# PCB-MicroVU.net
KiCad netlist of a schematic drawn in EAGLE
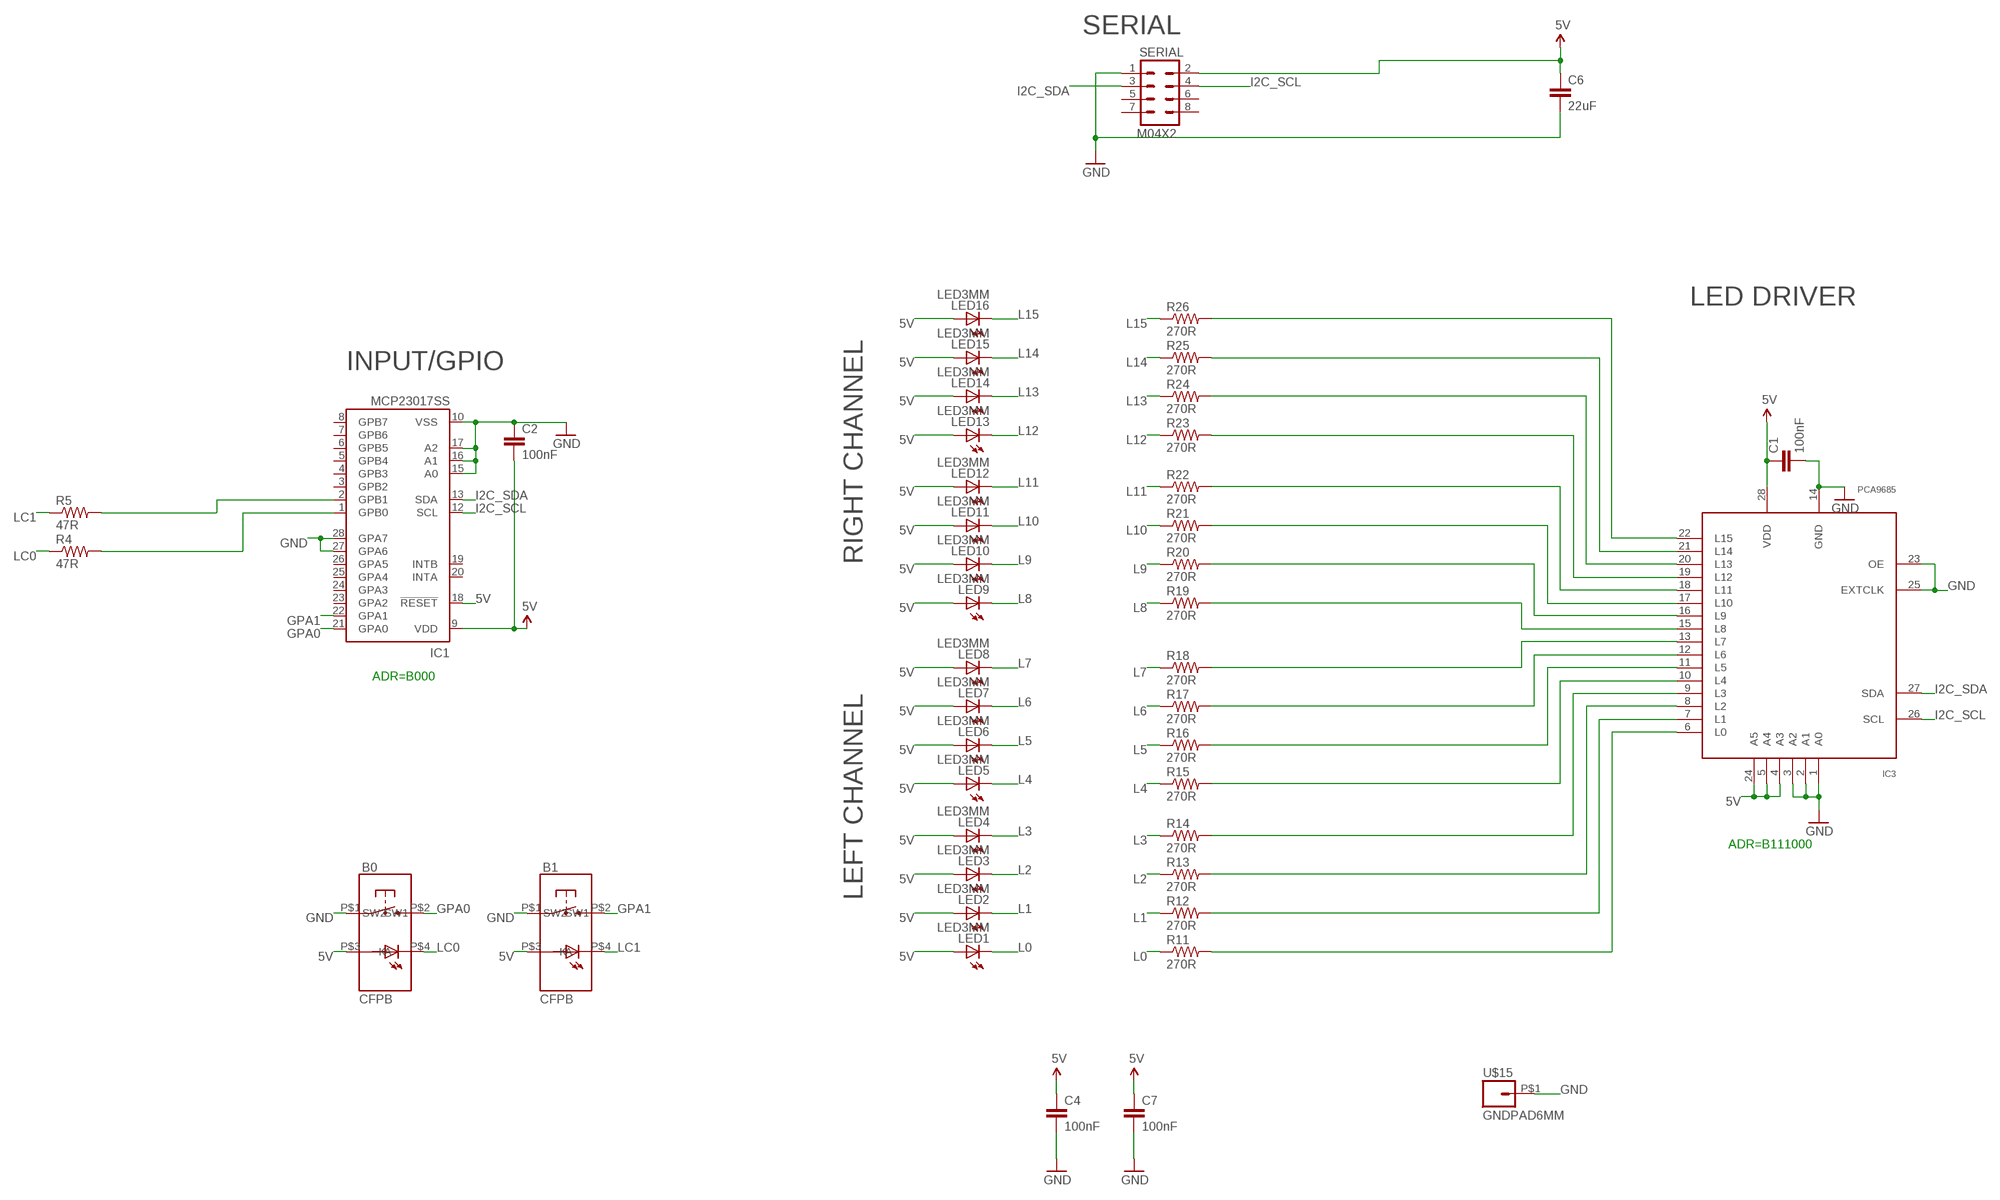
[diagram p0: schematic, sheet 1]

(export (version "E")
  (design (tool "Eeschema 10.0.6"))
  (components
    (comp (ref "B0")
      (value "CFPB")
      (footprint "eagle-import:CFPB-6_9MM")
      (libsource (lib "eagle-import") (part "CFPB"))
    )
    (comp (ref "B1")
      (value "CFPB")
      (footprint "eagle-import:CFPB-6_9MM")
      (libsource (lib "eagle-import") (part "CFPB"))
    )
    (comp (ref "C1")
      (value "100nF")
      (footprint "eagle-import:0603-CAP")
      (libsource (lib "eagle-import") (part "CAP0603-CAP"))
    )
    (comp (ref "C2")
      (value "100nF")
      (footprint "eagle-import:0603-CAP")
      (libsource (lib "eagle-import") (part "CAP0603-CAP"))
    )
    (comp (ref "C4")
      (value "100nF")
      (footprint "eagle-import:0603-CAP")
      (libsource (lib "eagle-import") (part "CAP0603-CAP"))
    )
    (comp (ref "C6")
      (value "22uF")
      (footprint "eagle-import:0805")
      (libsource (lib "eagle-import") (part "CAP0805"))
    )
    (comp (ref "C7")
      (value "100nF")
      (footprint "eagle-import:0603-CAP")
      (libsource (lib "eagle-import") (part "CAP0603-CAP"))
    )
    (comp (ref "IC1")
      (value "MCP23017SS")
      (footprint "eagle-import:SSOP28")
      (fields
        (field (name "MF") "MICROCHIP")
        (field (name "MPN") "MCP23017-E/SS")
        (field (name "MPN_1") "MCP23017-E/SS")
        (field (name "OC_FARNELL") "1467674")
        (field (name "OC_NEWARK") "31K2960")
      )
      (libsource (lib "eagle-import") (part "MCP23017SS"))
    )
    (comp (ref "IC3")
      (value "PCA9685")
      (footprint "eagle-import:TSSOP28")
      (libsource (lib "eagle-import") (part "PCA9685"))
    )
    (comp (ref "LED1")
      (value "LED3MM")
      (footprint "eagle-import:LED3MM")
      (libsource (lib "eagle-import") (part "LED3MM"))
    )
    (comp (ref "LED2")
      (value "LED3MM")
      (footprint "eagle-import:LED3MM")
      (libsource (lib "eagle-import") (part "LED3MM"))
    )
    (comp (ref "LED3")
      (value "LED3MM")
      (footprint "eagle-import:LED3MM")
      (libsource (lib "eagle-import") (part "LED3MM"))
    )
    (comp (ref "LED4")
      (value "LED3MM")
      (footprint "eagle-import:LED3MM")
      (libsource (lib "eagle-import") (part "LED3MM"))
    )
    (comp (ref "LED5")
      (value "LED3MM")
      (footprint "eagle-import:LED3MM")
      (libsource (lib "eagle-import") (part "LED3MM"))
    )
    (comp (ref "LED6")
      (value "LED3MM")
      (footprint "eagle-import:LED3MM")
      (libsource (lib "eagle-import") (part "LED3MM"))
    )
    (comp (ref "LED7")
      (value "LED3MM")
      (footprint "eagle-import:LED3MM")
      (libsource (lib "eagle-import") (part "LED3MM"))
    )
    (comp (ref "LED8")
      (value "LED3MM")
      (footprint "eagle-import:LED3MM")
      (libsource (lib "eagle-import") (part "LED3MM"))
    )
    (comp (ref "LED9")
      (value "LED3MM")
      (footprint "eagle-import:LED3MM")
      (libsource (lib "eagle-import") (part "LED3MM"))
    )
    (comp (ref "LED10")
      (value "LED3MM")
      (footprint "eagle-import:LED3MM")
      (libsource (lib "eagle-import") (part "LED3MM"))
    )
    (comp (ref "LED11")
      (value "LED3MM")
      (footprint "eagle-import:LED3MM")
      (libsource (lib "eagle-import") (part "LED3MM"))
    )
    (comp (ref "LED12")
      (value "LED3MM")
      (footprint "eagle-import:LED3MM")
      (libsource (lib "eagle-import") (part "LED3MM"))
    )
    (comp (ref "LED13")
      (value "LED3MM")
      (footprint "eagle-import:LED3MM")
      (libsource (lib "eagle-import") (part "LED3MM"))
    )
    (comp (ref "LED14")
      (value "LED3MM")
      (footprint "eagle-import:LED3MM")
      (libsource (lib "eagle-import") (part "LED3MM"))
    )
    (comp (ref "LED15")
      (value "LED3MM")
      (footprint "eagle-import:LED3MM")
      (libsource (lib "eagle-import") (part "LED3MM"))
    )
    (comp (ref "LED16")
      (value "LED3MM")
      (footprint "eagle-import:LED3MM")
      (libsource (lib "eagle-import") (part "LED3MM"))
    )
    (comp (ref "R4")
      (value "47R")
      (footprint "eagle-import:0603-RES")
      (libsource (lib "eagle-import") (part "RESISTOR0603-RES"))
    )
    (comp (ref "R5")
      (value "47R")
      (footprint "eagle-import:0603-RES")
      (libsource (lib "eagle-import") (part "RESISTOR0603-RES"))
    )
    (comp (ref "R11")
      (value "270R")
      (footprint "eagle-import:0603-RES")
      (libsource (lib "eagle-import") (part "RESISTOR0603-RES"))
    )
    (comp (ref "R12")
      (value "270R")
      (footprint "eagle-import:0603-RES")
      (libsource (lib "eagle-import") (part "RESISTOR0603-RES"))
    )
    (comp (ref "R13")
      (value "270R")
      (footprint "eagle-import:0603-RES")
      (libsource (lib "eagle-import") (part "RESISTOR0603-RES"))
    )
    (comp (ref "R14")
      (value "270R")
      (footprint "eagle-import:0603-RES")
      (libsource (lib "eagle-import") (part "RESISTOR0603-RES"))
    )
    (comp (ref "R15")
      (value "270R")
      (footprint "eagle-import:0603-RES")
      (libsource (lib "eagle-import") (part "RESISTOR0603-RES"))
    )
    (comp (ref "R16")
      (value "270R")
      (footprint "eagle-import:0603-RES")
      (libsource (lib "eagle-import") (part "RESISTOR0603-RES"))
    )
    (comp (ref "R17")
      (value "270R")
      (footprint "eagle-import:0603-RES")
      (libsource (lib "eagle-import") (part "RESISTOR0603-RES"))
    )
    (comp (ref "R18")
      (value "270R")
      (footprint "eagle-import:0603-RES")
      (libsource (lib "eagle-import") (part "RESISTOR0603-RES"))
    )
    (comp (ref "R19")
      (value "270R")
      (footprint "eagle-import:0603-RES")
      (libsource (lib "eagle-import") (part "RESISTOR0603-RES"))
    )
    (comp (ref "R20")
      (value "270R")
      (footprint "eagle-import:0603-RES")
      (libsource (lib "eagle-import") (part "RESISTOR0603-RES"))
    )
    (comp (ref "R21")
      (value "270R")
      (footprint "eagle-import:0603-RES")
      (libsource (lib "eagle-import") (part "RESISTOR0603-RES"))
    )
    (comp (ref "R22")
      (value "270R")
      (footprint "eagle-import:0603-RES")
      (libsource (lib "eagle-import") (part "RESISTOR0603-RES"))
    )
    (comp (ref "R23")
      (value "270R")
      (footprint "eagle-import:0603-RES")
      (libsource (lib "eagle-import") (part "RESISTOR0603-RES"))
    )
    (comp (ref "R24")
      (value "270R")
      (footprint "eagle-import:0603-RES")
      (libsource (lib "eagle-import") (part "RESISTOR0603-RES"))
    )
    (comp (ref "R25")
      (value "270R")
      (footprint "eagle-import:0603-RES")
      (libsource (lib "eagle-import") (part "RESISTOR0603-RES"))
    )
    (comp (ref "R26")
      (value "270R")
      (footprint "eagle-import:0603-RES")
      (libsource (lib "eagle-import") (part "RESISTOR0603-RES"))
    )
    (comp (ref "SERIAL")
      (value "M04X2")
      (footprint "eagle-import:2X4")
      (libsource (lib "eagle-import") (part "M04X2"))
    )
    (comp (ref "U$15")
      (value "GNDPAD6MM")
      (footprint "eagle-import:3.2MMPAD6MM")
      (libsource (lib "eagle-import") (part "GNDPAD6MM"))
    )
  )
  (nets
    (net (code "1") (name "/GPA0") (class "Default")
      (node (ref "B0") (pin "P$2") (pinfunction "SW2_P$2") (pintype "bidirectional"))
      (node (ref "IC1") (pin "21") (pinfunction "GPA0_21") (pintype "bidirectional"))
    )
    (net (code "2") (name "/GPA1") (class "Default")
      (node (ref "B1") (pin "P$2") (pinfunction "SW2_P$2") (pintype "bidirectional"))
      (node (ref "IC1") (pin "22") (pinfunction "GPA1_22") (pintype "bidirectional"))
    )
    (net (code "3") (name "/I2C_SCL") (class "Default")
      (node (ref "IC1") (pin "12") (pinfunction "SCL_12") (pintype "input"))
      (node (ref "IC3") (pin "26") (pinfunction "SCL_26") (pintype "input"))
      (node (ref "SERIAL") (pin "4") (pinfunction "4_4") (pintype "passive"))
    )
    (net (code "4") (name "/I2C_SDA") (class "Default")
      (node (ref "IC1") (pin "13") (pinfunction "SDA_13") (pintype "bidirectional"))
      (node (ref "IC3") (pin "27") (pinfunction "SDA_27") (pintype "input"))
      (node (ref "SERIAL") (pin "3") (pinfunction "3_3") (pintype "passive"))
    )
    (net (code "5") (name "/L0") (class "Default")
      (node (ref "LED1") (pin "K") (pinfunction "C_K") (pintype "passive"))
      (node (ref "R11") (pin "1") (pinfunction "1_1") (pintype "passive"))
    )
    (net (code "6") (name "/L1") (class "Default")
      (node (ref "LED2") (pin "K") (pinfunction "C_K") (pintype "passive"))
      (node (ref "R12") (pin "1") (pinfunction "1_1") (pintype "passive"))
    )
    (net (code "7") (name "/L2") (class "Default")
      (node (ref "LED3") (pin "K") (pinfunction "C_K") (pintype "passive"))
      (node (ref "R13") (pin "1") (pinfunction "1_1") (pintype "passive"))
    )
    (net (code "8") (name "/L3") (class "Default")
      (node (ref "LED4") (pin "K") (pinfunction "C_K") (pintype "passive"))
      (node (ref "R14") (pin "1") (pinfunction "1_1") (pintype "passive"))
    )
    (net (code "9") (name "/L4") (class "Default")
      (node (ref "LED5") (pin "K") (pinfunction "C_K") (pintype "passive"))
      (node (ref "R15") (pin "1") (pinfunction "1_1") (pintype "passive"))
    )
    (net (code "10") (name "/L5") (class "Default")
      (node (ref "LED6") (pin "K") (pinfunction "C_K") (pintype "passive"))
      (node (ref "R16") (pin "1") (pinfunction "1_1") (pintype "passive"))
    )
    (net (code "11") (name "/L6") (class "Default")
      (node (ref "LED7") (pin "K") (pinfunction "C_K") (pintype "passive"))
      (node (ref "R17") (pin "1") (pinfunction "1_1") (pintype "passive"))
    )
    (net (code "12") (name "/L7") (class "Default")
      (node (ref "LED8") (pin "K") (pinfunction "C_K") (pintype "passive"))
      (node (ref "R18") (pin "1") (pinfunction "1_1") (pintype "passive"))
    )
    (net (code "13") (name "/L8") (class "Default")
      (node (ref "LED9") (pin "K") (pinfunction "C_K") (pintype "passive"))
      (node (ref "R19") (pin "1") (pinfunction "1_1") (pintype "passive"))
    )
    (net (code "14") (name "/L9") (class "Default")
      (node (ref "LED10") (pin "K") (pinfunction "C_K") (pintype "passive"))
      (node (ref "R20") (pin "1") (pinfunction "1_1") (pintype "passive"))
    )
    (net (code "15") (name "/L10") (class "Default")
      (node (ref "LED11") (pin "K") (pinfunction "C_K") (pintype "passive"))
      (node (ref "R21") (pin "1") (pinfunction "1_1") (pintype "passive"))
    )
    (net (code "16") (name "/L11") (class "Default")
      (node (ref "LED12") (pin "K") (pinfunction "C_K") (pintype "passive"))
      (node (ref "R22") (pin "1") (pinfunction "1_1") (pintype "passive"))
    )
    (net (code "17") (name "/L12") (class "Default")
      (node (ref "LED13") (pin "K") (pinfunction "C_K") (pintype "passive"))
      (node (ref "R23") (pin "1") (pinfunction "1_1") (pintype "passive"))
    )
    (net (code "18") (name "/L13") (class "Default")
      (node (ref "LED14") (pin "K") (pinfunction "C_K") (pintype "passive"))
      (node (ref "R24") (pin "1") (pinfunction "1_1") (pintype "passive"))
    )
    (net (code "19") (name "/L14") (class "Default")
      (node (ref "LED15") (pin "K") (pinfunction "C_K") (pintype "passive"))
      (node (ref "R25") (pin "1") (pinfunction "1_1") (pintype "passive"))
    )
    (net (code "20") (name "/L15") (class "Default")
      (node (ref "LED16") (pin "K") (pinfunction "C_K") (pintype "passive"))
      (node (ref "R26") (pin "1") (pinfunction "1_1") (pintype "passive"))
    )
    (net (code "21") (name "/LC0") (class "Default")
      (node (ref "B0") (pin "P$4") (pinfunction "K_P$4") (pintype "bidirectional"))
      (node (ref "R4") (pin "1") (pinfunction "1_1") (pintype "passive"))
    )
    (net (code "22") (name "/LC1") (class "Default")
      (node (ref "B1") (pin "P$4") (pinfunction "K_P$4") (pintype "bidirectional"))
      (node (ref "R5") (pin "1") (pinfunction "1_1") (pintype "passive"))
    )
    (net (code "23") (name "5V") (class "Default")
      (node (ref "B0") (pin "P$3") (pinfunction "A_P$3") (pintype "bidirectional"))
      (node (ref "B1") (pin "P$3") (pinfunction "A_P$3") (pintype "bidirectional"))
      (node (ref "C1") (pin "1") (pinfunction "1_1") (pintype "passive"))
      (node (ref "C2") (pin "2") (pinfunction "2_2") (pintype "passive"))
      (node (ref "C4") (pin "1") (pinfunction "1_1") (pintype "passive"))
      (node (ref "C6") (pin "1") (pinfunction "1_1") (pintype "passive"))
      (node (ref "C7") (pin "1") (pinfunction "1_1") (pintype "passive"))
      (node (ref "IC1") (pin "18") (pinfunction "~{RESET}_18") (pintype "input"))
      (node (ref "IC1") (pin "9") (pinfunction "VDD_9") (pintype "power_in"))
      (node (ref "IC3") (pin "24") (pinfunction "A5_24") (pintype "input"))
      (node (ref "IC3") (pin "28") (pinfunction "VDD_28") (pintype "power_in"))
      (node (ref "IC3") (pin "4") (pinfunction "A3_4") (pintype "input"))
      (node (ref "IC3") (pin "5") (pinfunction "A4_5") (pintype "input"))
      (node (ref "LED1") (pin "A") (pinfunction "A_A") (pintype "passive"))
      (node (ref "LED10") (pin "A") (pinfunction "A_A") (pintype "passive"))
      (node (ref "LED11") (pin "A") (pinfunction "A_A") (pintype "passive"))
      (node (ref "LED12") (pin "A") (pinfunction "A_A") (pintype "passive"))
      (node (ref "LED13") (pin "A") (pinfunction "A_A") (pintype "passive"))
      (node (ref "LED14") (pin "A") (pinfunction "A_A") (pintype "passive"))
      (node (ref "LED15") (pin "A") (pinfunction "A_A") (pintype "passive"))
      (node (ref "LED16") (pin "A") (pinfunction "A_A") (pintype "passive"))
      (node (ref "LED2") (pin "A") (pinfunction "A_A") (pintype "passive"))
      (node (ref "LED3") (pin "A") (pinfunction "A_A") (pintype "passive"))
      (node (ref "LED4") (pin "A") (pinfunction "A_A") (pintype "passive"))
      (node (ref "LED5") (pin "A") (pinfunction "A_A") (pintype "passive"))
      (node (ref "LED6") (pin "A") (pinfunction "A_A") (pintype "passive"))
      (node (ref "LED7") (pin "A") (pinfunction "A_A") (pintype "passive"))
      (node (ref "LED8") (pin "A") (pinfunction "A_A") (pintype "passive"))
      (node (ref "LED9") (pin "A") (pinfunction "A_A") (pintype "passive"))
      (node (ref "SERIAL") (pin "2") (pinfunction "2_2") (pintype "passive"))
    )
    (net (code "24") (name "GND") (class "Default")
      (node (ref "B0") (pin "P$1") (pinfunction "SW1_P$1") (pintype "bidirectional"))
      (node (ref "B1") (pin "P$1") (pinfunction "SW1_P$1") (pintype "bidirectional"))
      (node (ref "C1") (pin "2") (pinfunction "2_2") (pintype "passive"))
      (node (ref "C2") (pin "1") (pinfunction "1_1") (pintype "passive"))
      (node (ref "C4") (pin "2") (pinfunction "2_2") (pintype "passive"))
      (node (ref "C6") (pin "2") (pinfunction "2_2") (pintype "passive"))
      (node (ref "C7") (pin "2") (pinfunction "2_2") (pintype "passive"))
      (node (ref "IC1") (pin "10") (pinfunction "VSS_10") (pintype "power_in"))
      (node (ref "IC1") (pin "15") (pinfunction "A0_15") (pintype "input"))
      (node (ref "IC1") (pin "16") (pinfunction "A1_16") (pintype "input"))
      (node (ref "IC1") (pin "17") (pinfunction "A2_17") (pintype "input"))
      (node (ref "IC1") (pin "27") (pinfunction "GPA6_27") (pintype "bidirectional"))
      (node (ref "IC1") (pin "28") (pinfunction "GPA7_28") (pintype "bidirectional"))
      (node (ref "IC3") (pin "1") (pinfunction "A0_1") (pintype "input"))
      (node (ref "IC3") (pin "14") (pinfunction "GND_14") (pintype "power_in"))
      (node (ref "IC3") (pin "2") (pinfunction "A1_2") (pintype "input"))
      (node (ref "IC3") (pin "23") (pinfunction "OE_23") (pintype "input"))
      (node (ref "IC3") (pin "25") (pinfunction "EXTCLK_25") (pintype "input"))
      (node (ref "IC3") (pin "3") (pinfunction "A2_3") (pintype "input"))
      (node (ref "SERIAL") (pin "1") (pinfunction "1_1") (pintype "passive"))
      (node (ref "U$15") (pin "P$1") (pinfunction "1_P$1") (pintype "passive"))
    )
    (net (code "25") (name "Net-(IC1-GPB0)") (class "Default")
      (node (ref "IC1") (pin "1") (pinfunction "GPB0_1") (pintype "bidirectional"))
      (node (ref "R4") (pin "2") (pinfunction "2_2") (pintype "passive"))
    )
    (net (code "26") (name "Net-(IC1-GPB1)") (class "Default")
      (node (ref "IC1") (pin "2") (pinfunction "GPB1_2") (pintype "bidirectional"))
      (node (ref "R5") (pin "2") (pinfunction "2_2") (pintype "passive"))
    )
    (net (code "27") (name "Net-(IC3-L0)") (class "Default")
      (node (ref "IC3") (pin "6") (pinfunction "L0_6") (pintype "output"))
      (node (ref "R11") (pin "2") (pinfunction "2_2") (pintype "passive"))
    )
    (net (code "28") (name "Net-(IC3-L1)") (class "Default")
      (node (ref "IC3") (pin "7") (pinfunction "L1_7") (pintype "output"))
      (node (ref "R12") (pin "2") (pinfunction "2_2") (pintype "passive"))
    )
    (net (code "29") (name "Net-(IC3-L2)") (class "Default")
      (node (ref "IC3") (pin "8") (pinfunction "L2_8") (pintype "output"))
      (node (ref "R13") (pin "2") (pinfunction "2_2") (pintype "passive"))
    )
    (net (code "30") (name "Net-(IC3-L3)") (class "Default")
      (node (ref "IC3") (pin "9") (pinfunction "L3_9") (pintype "output"))
      (node (ref "R14") (pin "2") (pinfunction "2_2") (pintype "passive"))
    )
    (net (code "31") (name "Net-(IC3-L4)") (class "Default")
      (node (ref "IC3") (pin "10") (pinfunction "L4_10") (pintype "output"))
      (node (ref "R15") (pin "2") (pinfunction "2_2") (pintype "passive"))
    )
    (net (code "32") (name "Net-(IC3-L5)") (class "Default")
      (node (ref "IC3") (pin "11") (pinfunction "L5_11") (pintype "output"))
      (node (ref "R16") (pin "2") (pinfunction "2_2") (pintype "passive"))
    )
    (net (code "33") (name "Net-(IC3-L6)") (class "Default")
      (node (ref "IC3") (pin "12") (pinfunction "L6_12") (pintype "output"))
      (node (ref "R17") (pin "2") (pinfunction "2_2") (pintype "passive"))
    )
    (net (code "34") (name "Net-(IC3-L7)") (class "Default")
      (node (ref "IC3") (pin "13") (pinfunction "L7_13") (pintype "output"))
      (node (ref "R18") (pin "2") (pinfunction "2_2") (pintype "passive"))
    )
    (net (code "35") (name "Net-(IC3-L8)") (class "Default")
      (node (ref "IC3") (pin "15") (pinfunction "L8_15") (pintype "output"))
      (node (ref "R19") (pin "2") (pinfunction "2_2") (pintype "passive"))
    )
    (net (code "36") (name "Net-(IC3-L9)") (class "Default")
      (node (ref "IC3") (pin "16") (pinfunction "L9_16") (pintype "output"))
      (node (ref "R20") (pin "2") (pinfunction "2_2") (pintype "passive"))
    )
    (net (code "37") (name "Net-(IC3-L10)") (class "Default")
      (node (ref "IC3") (pin "17") (pinfunction "L10_17") (pintype "output"))
      (node (ref "R21") (pin "2") (pinfunction "2_2") (pintype "passive"))
    )
    (net (code "38") (name "Net-(IC3-L11)") (class "Default")
      (node (ref "IC3") (pin "18") (pinfunction "L11_18") (pintype "output"))
      (node (ref "R22") (pin "2") (pinfunction "2_2") (pintype "passive"))
    )
    (net (code "39") (name "Net-(IC3-L12)") (class "Default")
      (node (ref "IC3") (pin "19") (pinfunction "L12_19") (pintype "output"))
      (node (ref "R23") (pin "2") (pinfunction "2_2") (pintype "passive"))
    )
    (net (code "40") (name "Net-(IC3-L13)") (class "Default")
      (node (ref "IC3") (pin "20") (pinfunction "L13_20") (pintype "output"))
      (node (ref "R24") (pin "2") (pinfunction "2_2") (pintype "passive"))
    )
    (net (code "41") (name "Net-(IC3-L14)") (class "Default")
      (node (ref "IC3") (pin "21") (pinfunction "L14_21") (pintype "output"))
      (node (ref "R25") (pin "2") (pinfunction "2_2") (pintype "passive"))
    )
    (net (code "42") (name "Net-(IC3-L15)") (class "Default")
      (node (ref "IC3") (pin "22") (pinfunction "L15_22") (pintype "output"))
      (node (ref "R26") (pin "2") (pinfunction "2_2") (pintype "passive"))
    )
    (net (code "43") (name "unconnected-(IC1-GPA2-Pad23)") (class "Default")
      (node (ref "IC1") (pin "23") (pinfunction "GPA2_23") (pintype "bidirectional"))
    )
    (net (code "44") (name "unconnected-(IC1-GPA3-Pad24)") (class "Default")
      (node (ref "IC1") (pin "24") (pinfunction "GPA3_24") (pintype "bidirectional"))
    )
    (net (code "45") (name "unconnected-(IC1-GPA4-Pad25)") (class "Default")
      (node (ref "IC1") (pin "25") (pinfunction "GPA4_25") (pintype "bidirectional"))
    )
    (net (code "46") (name "unconnected-(IC1-GPA5-Pad26)") (class "Default")
      (node (ref "IC1") (pin "26") (pinfunction "GPA5_26") (pintype "bidirectional"))
    )
    (net (code "47") (name "unconnected-(IC1-GPB2-Pad3)") (class "Default")
      (node (ref "IC1") (pin "3") (pinfunction "GPB2_3") (pintype "bidirectional"))
    )
    (net (code "48") (name "unconnected-(IC1-GPB3-Pad4)") (class "Default")
      (node (ref "IC1") (pin "4") (pinfunction "GPB3_4") (pintype "bidirectional"))
    )
    (net (code "49") (name "unconnected-(IC1-GPB4-Pad5)") (class "Default")
      (node (ref "IC1") (pin "5") (pinfunction "GPB4_5") (pintype "bidirectional"))
    )
    (net (code "50") (name "unconnected-(IC1-GPB5-Pad6)") (class "Default")
      (node (ref "IC1") (pin "6") (pinfunction "GPB5_6") (pintype "bidirectional"))
    )
    (net (code "51") (name "unconnected-(IC1-GPB6-Pad7)") (class "Default")
      (node (ref "IC1") (pin "7") (pinfunction "GPB6_7") (pintype "bidirectional"))
    )
    (net (code "52") (name "unconnected-(IC1-GPB7-Pad8)") (class "Default")
      (node (ref "IC1") (pin "8") (pinfunction "GPB7_8") (pintype "bidirectional"))
    )
    (net (code "53") (name "unconnected-(IC1-INTA-Pad20)") (class "Default")
      (node (ref "IC1") (pin "20") (pinfunction "INTA_20") (pintype "output"))
    )
    (net (code "54") (name "unconnected-(IC1-INTB-Pad19)") (class "Default")
      (node (ref "IC1") (pin "19") (pinfunction "INTB_19") (pintype "output"))
    )
    (net (code "55") (name "unconnected-(SERIAL-Pad5)") (class "Default")
      (node (ref "SERIAL") (pin "5") (pinfunction "5_5") (pintype "passive"))
    )
    (net (code "56") (name "unconnected-(SERIAL-Pad6)") (class "Default")
      (node (ref "SERIAL") (pin "6") (pinfunction "6_6") (pintype "passive"))
    )
    (net (code "57") (name "unconnected-(SERIAL-Pad7)") (class "Default")
      (node (ref "SERIAL") (pin "7") (pinfunction "7_7") (pintype "passive"))
    )
    (net (code "58") (name "unconnected-(SERIAL-Pad8)") (class "Default")
      (node (ref "SERIAL") (pin "8") (pinfunction "8_8") (pintype "passive"))
    )
  )
)
